# PinscapePico_KL25Z_Adapter_-_PCA9555_vsn.net
KiCad netlist of a schematic drawn in EAGLE
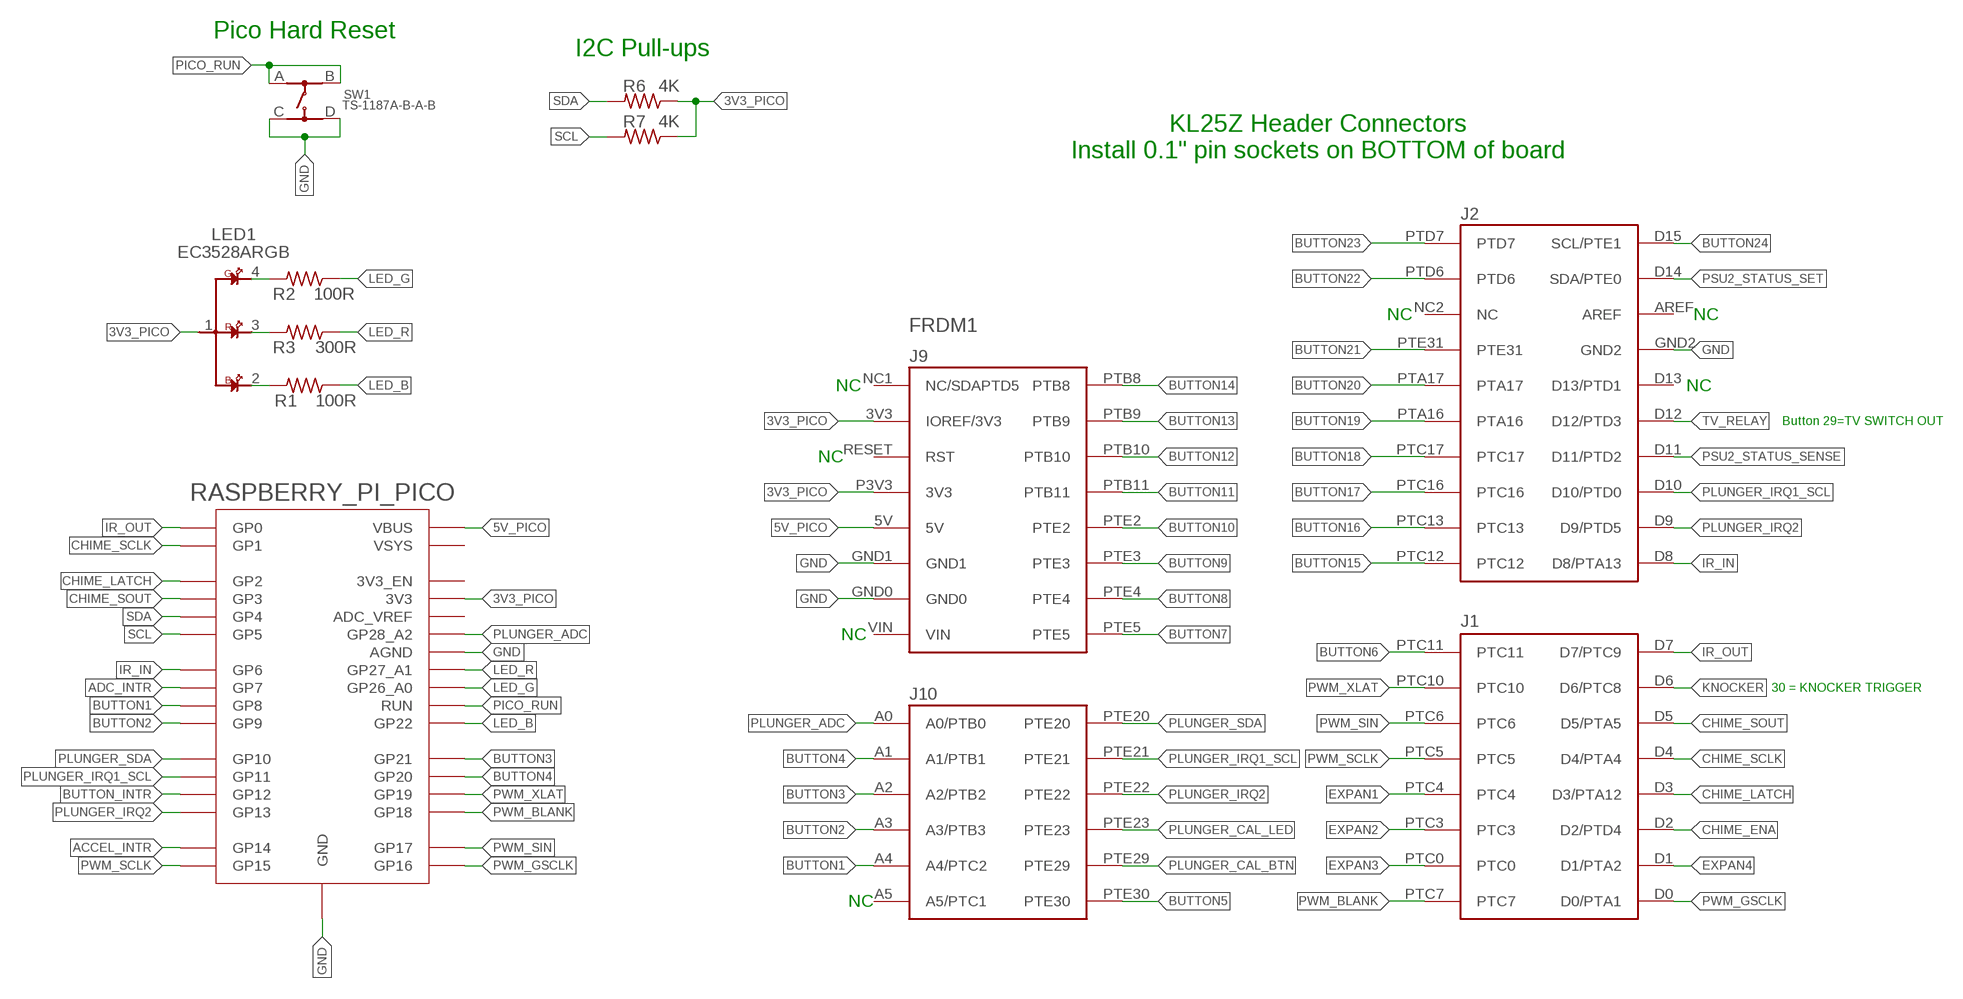
[diagram p0: schematic, sheet 1]
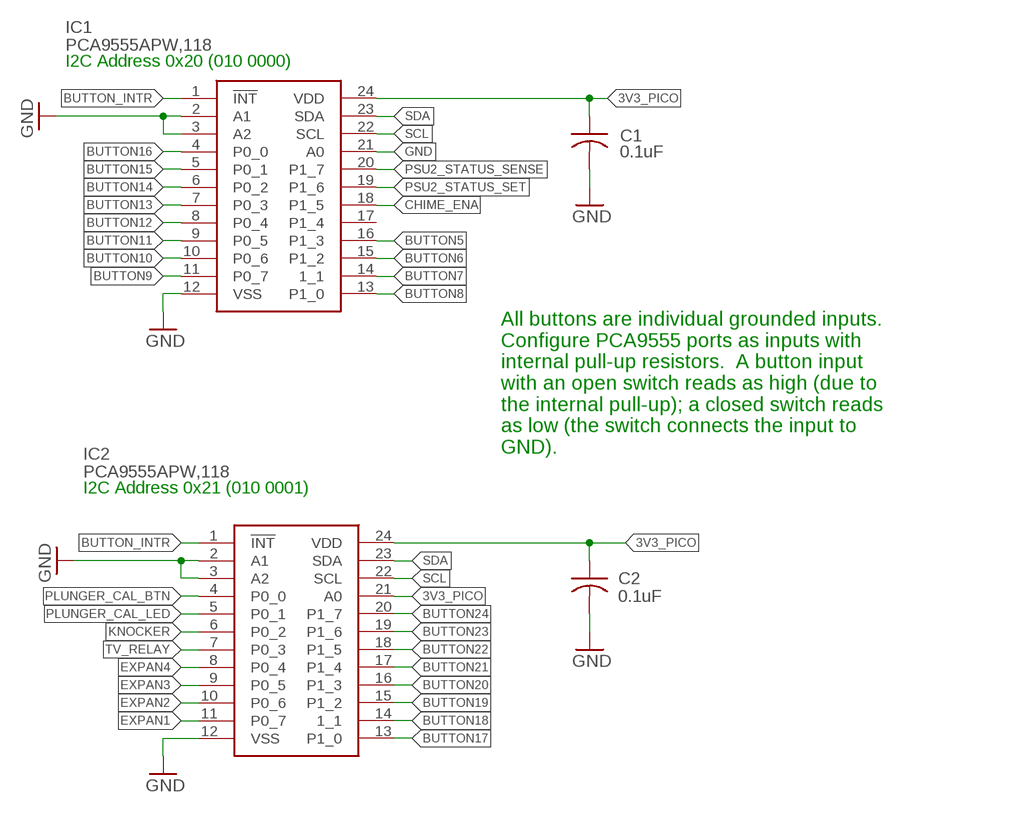
[diagram p1: schematic, sheet 2]
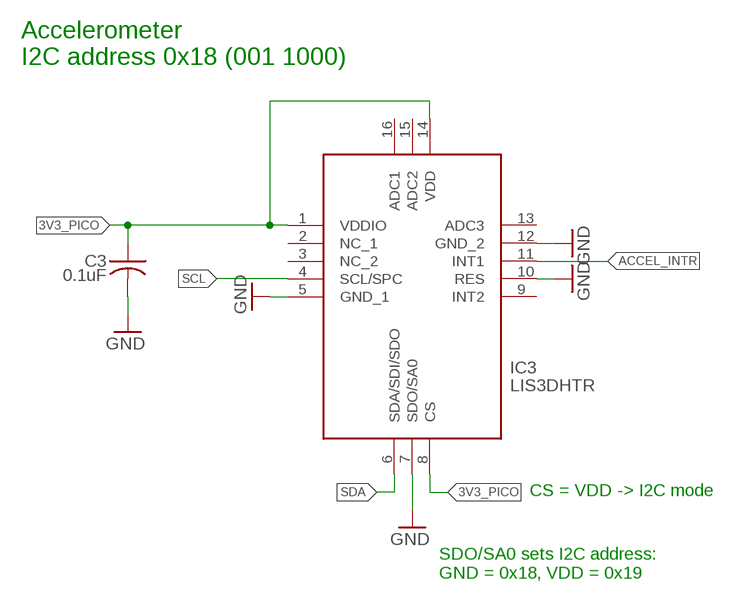
[diagram p2: schematic, sheet 3]
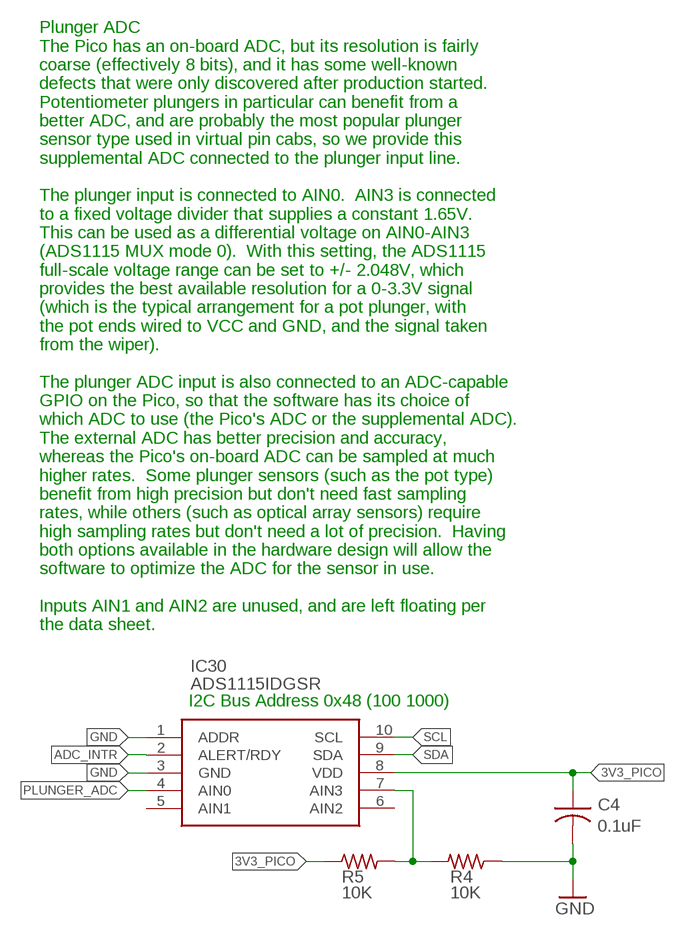
[diagram p3: schematic, sheet 4]

(export (version "E")
  (design (tool "Eeschema 10.0.6"))
  (components
    (comp (ref "C3")
      (value "0.1uF")
      (footprint "eagle-import:C1206")
      (libsource (lib "eagle-import") (part "C-USC1206"))
    )
    (comp (ref "IC3")
      (value "LIS3DHTR")
      (footprint "eagle-import:LIS3DHTR")
      (fields (field (name "MOUSER_PART_NUMBER") "511-LIS3DHTR"))
      (libsource (lib "eagle-import") (part "LIS3DHTR"))
    )
    (comp (ref "FRDM1")
      (value "KL25Z")
      (footprint "eagle-import:FRDM_KL25Z_NORMAL")
      (libsource (lib "eagle-import") (part "FRDM-KL25ZNORMAL"))
    )
    (comp (ref "LED1")
      (value "EC3528ARGB")
      (footprint "eagle-import:EC3528ARGB")
      (libsource (lib "eagle-import") (part "EC3528ARGB"))
    )
    (comp (ref "R1")
      (value "100R")
      (footprint "eagle-import:R1206")
      (libsource (lib "eagle-import") (part "R-US_R1206"))
    )
    (comp (ref "R2")
      (value "100R")
      (footprint "eagle-import:R1206")
      (libsource (lib "eagle-import") (part "R-US_R1206"))
    )
    (comp (ref "R3")
      (value "300R")
      (footprint "eagle-import:R1206")
      (libsource (lib "eagle-import") (part "R-US_R1206"))
    )
    (comp (ref "R6")
      (value "4K")
      (footprint "eagle-import:R1206")
      (libsource (lib "eagle-import") (part "R-US_R1206"))
    )
    (comp (ref "R7")
      (value "4K")
      (footprint "eagle-import:R1206")
      (libsource (lib "eagle-import") (part "R-US_R1206"))
    )
    (comp (ref "RASPBERRY_PI_PICO")
      (value "RPI_PICO_NO_DEBUG")
      (footprint "eagle-import:RPI_PICO_TH_NO_DEBUG")
      (libsource (lib "eagle-import") (part "RPI_PICO_NO_DEBUG"))
    )
    (comp (ref "SW1")
      (value "TS-1187A-B-A-B")
      (footprint "eagle-import:TS-1187A-B-A-B")
      (libsource (lib "eagle-import") (part "TS-1187A-B-A-B"))
    )
    (comp (ref "C4")
      (value "0.1uF")
      (footprint "eagle-import:C1206")
      (libsource (lib "eagle-import") (part "C-USC1206"))
    )
    (comp (ref "IC30")
      (value "ADS1115IDGSR")
      (footprint "eagle-import:SOP50P490X110-10N")
      (fields (field (name "MOUSER_PART_NUMBER") "595-ADS1115IDGSR"))
      (libsource (lib "eagle-import") (part "ADS1115IDGSR"))
    )
    (comp (ref "R4")
      (value "10K")
      (footprint "eagle-import:R1206")
      (libsource (lib "eagle-import") (part "R-US_R1206"))
    )
    (comp (ref "R5")
      (value "10K")
      (footprint "eagle-import:R1206")
      (libsource (lib "eagle-import") (part "R-US_R1206"))
    )
    (comp (ref "C1")
      (value "0.1uF")
      (footprint "eagle-import:C1206")
      (libsource (lib "eagle-import") (part "C-USC1206"))
    )
    (comp (ref "C2")
      (value "0.1uF")
      (footprint "eagle-import:C1206")
      (libsource (lib "eagle-import") (part "C-USC1206"))
    )
    (comp (ref "IC1")
      (value "PCA9555APW,118")
      (footprint "eagle-import:SOP65P640X110-24N")
      (fields (field (name "MOUSER_PART_NUMBER") "771-PCA9555APW118"))
      (libsource (lib "eagle-import") (part "PCA9555APW,118"))
    )
    (comp (ref "IC2")
      (value "PCA9555APW,118")
      (footprint "eagle-import:SOP65P640X110-24N")
      (fields (field (name "MOUSER_PART_NUMBER") "771-PCA9555APW118"))
      (libsource (lib "eagle-import") (part "PCA9555APW,118"))
    )
  )
  (nets
    (net (code "1") (name "3V3_PICO") (class "Default")
      (node (ref "C1") (pin "1") (pinfunction "1_1") (pintype "passive"))
      (node (ref "C2") (pin "1") (pinfunction "1_1") (pintype "passive"))
      (node (ref "C3") (pin "1") (pinfunction "1_1") (pintype "passive"))
      (node (ref "C4") (pin "1") (pinfunction "1_1") (pintype "passive"))
      (node (ref "FRDM1") (pin "3V3") (pinfunction "IOREF/3V3_3V3") (pintype "bidirectional"))
      (node (ref "FRDM1") (pin "P3V3") (pinfunction "3V3_P3V3") (pintype "bidirectional"))
      (node (ref "IC1") (pin "24") (pinfunction "VDD_24") (pintype "bidirectional"))
      (node (ref "IC2") (pin "21") (pinfunction "A0_21") (pintype "bidirectional"))
      (node (ref "IC2") (pin "24") (pinfunction "VDD_24") (pintype "bidirectional"))
      (node (ref "IC3") (pin "1") (pinfunction "VDDIO_1") (pintype "power_in"))
      (node (ref "IC3") (pin "14") (pinfunction "VDD_14") (pintype "power_in"))
      (node (ref "IC3") (pin "8") (pinfunction "CS_8") (pintype "input"))
      (node (ref "IC30") (pin "8") (pinfunction "VDD_8") (pintype "bidirectional"))
      (node (ref "LED1") (pin "1") (pinfunction "1_1") (pintype "bidirectional"))
      (node (ref "R5") (pin "1") (pinfunction "1_1") (pintype "passive"))
      (node (ref "R6") (pin "1") (pinfunction "1_1") (pintype "passive"))
      (node (ref "R7") (pin "1") (pinfunction "1_1") (pintype "passive"))
      (node (ref "RASPBERRY_PI_PICO") (pin "3V3") (pinfunction "3V3_3V3") (pintype "bidirectional"))
    )
    (net (code "2") (name "5V_PICO") (class "Default")
      (node (ref "FRDM1") (pin "5V") (pinfunction "5V_5V") (pintype "bidirectional"))
      (node (ref "RASPBERRY_PI_PICO") (pin "VBUS") (pinfunction "VBUS_VBUS") (pintype "bidirectional"))
    )
    (net (code "3") (name "ACCEL_INTR") (class "Default")
      (node (ref "IC3") (pin "11") (pinfunction "INT1_11") (pintype "input"))
      (node (ref "RASPBERRY_PI_PICO") (pin "GP14") (pinfunction "GP14_GP14") (pintype "bidirectional"))
    )
    (net (code "4") (name "ADC_INTR") (class "Default")
      (node (ref "IC30") (pin "2") (pinfunction "ALERT/RDY_2") (pintype "bidirectional"))
      (node (ref "RASPBERRY_PI_PICO") (pin "GP7") (pinfunction "GP7_GP7") (pintype "bidirectional"))
    )
    (net (code "5") (name "BUTTON1") (class "Default")
      (node (ref "FRDM1") (pin "A4") (pinfunction "A4/PTC2_A4") (pintype "bidirectional"))
      (node (ref "RASPBERRY_PI_PICO") (pin "GP8") (pinfunction "GP8_GP8") (pintype "bidirectional"))
    )
    (net (code "6") (name "BUTTON2") (class "Default")
      (node (ref "FRDM1") (pin "A3") (pinfunction "A3/PTB3_A3") (pintype "bidirectional"))
      (node (ref "RASPBERRY_PI_PICO") (pin "GP9") (pinfunction "GP9_GP9") (pintype "bidirectional"))
    )
    (net (code "7") (name "BUTTON3") (class "Default")
      (node (ref "FRDM1") (pin "A2") (pinfunction "A2/PTB2_A2") (pintype "bidirectional"))
      (node (ref "RASPBERRY_PI_PICO") (pin "GP21") (pinfunction "GP21_GP21") (pintype "bidirectional"))
    )
    (net (code "8") (name "BUTTON4") (class "Default")
      (node (ref "FRDM1") (pin "A1") (pinfunction "A1/PTB1_A1") (pintype "bidirectional"))
      (node (ref "RASPBERRY_PI_PICO") (pin "GP20") (pinfunction "GP20_GP20") (pintype "bidirectional"))
    )
    (net (code "9") (name "BUTTON5") (class "Default")
      (node (ref "FRDM1") (pin "PTE30") (pinfunction "PTE30_PTE30") (pintype "bidirectional"))
      (node (ref "IC1") (pin "16") (pinfunction "P1_3_16") (pintype "bidirectional"))
    )
    (net (code "10") (name "BUTTON6") (class "Default")
      (node (ref "FRDM1") (pin "PTC11") (pinfunction "PTC11_PTC11") (pintype "bidirectional"))
      (node (ref "IC1") (pin "15") (pinfunction "P1_2_15") (pintype "bidirectional"))
    )
    (net (code "11") (name "BUTTON7") (class "Default")
      (node (ref "FRDM1") (pin "PTE5") (pinfunction "PTE5_PTE5") (pintype "bidirectional"))
      (node (ref "IC1") (pin "14") (pinfunction "1_1_14") (pintype "bidirectional"))
    )
    (net (code "12") (name "BUTTON8") (class "Default")
      (node (ref "FRDM1") (pin "PTE4") (pinfunction "PTE4_PTE4") (pintype "bidirectional"))
      (node (ref "IC1") (pin "13") (pinfunction "P1_0_13") (pintype "bidirectional"))
    )
    (net (code "13") (name "BUTTON9") (class "Default")
      (node (ref "FRDM1") (pin "PTE3") (pinfunction "PTE3_PTE3") (pintype "bidirectional"))
      (node (ref "IC1") (pin "11") (pinfunction "P0_7_11") (pintype "bidirectional"))
    )
    (net (code "14") (name "BUTTON10") (class "Default")
      (node (ref "FRDM1") (pin "PTE2") (pinfunction "PTE2_PTE2") (pintype "bidirectional"))
      (node (ref "IC1") (pin "10") (pinfunction "P0_6_10") (pintype "bidirectional"))
    )
    (net (code "15") (name "BUTTON11") (class "Default")
      (node (ref "FRDM1") (pin "PTB11") (pinfunction "PTB11_PTB11") (pintype "bidirectional"))
      (node (ref "IC1") (pin "9") (pinfunction "P0_5_9") (pintype "bidirectional"))
    )
    (net (code "16") (name "BUTTON12") (class "Default")
      (node (ref "FRDM1") (pin "PTB10") (pinfunction "PTB10_PTB10") (pintype "bidirectional"))
      (node (ref "IC1") (pin "8") (pinfunction "P0_4_8") (pintype "bidirectional"))
    )
    (net (code "17") (name "BUTTON13") (class "Default")
      (node (ref "FRDM1") (pin "PTB9") (pinfunction "PTB9_PTB9") (pintype "bidirectional"))
      (node (ref "IC1") (pin "7") (pinfunction "P0_3_7") (pintype "bidirectional"))
    )
    (net (code "18") (name "BUTTON14") (class "Default")
      (node (ref "FRDM1") (pin "PTB8") (pinfunction "PTB8_PTB8") (pintype "bidirectional"))
      (node (ref "IC1") (pin "6") (pinfunction "P0_2_6") (pintype "bidirectional"))
    )
    (net (code "19") (name "BUTTON15") (class "Default")
      (node (ref "FRDM1") (pin "PTC12") (pinfunction "PTC12_PTC12") (pintype "bidirectional"))
      (node (ref "IC1") (pin "5") (pinfunction "P0_1_5") (pintype "bidirectional"))
    )
    (net (code "20") (name "BUTTON16") (class "Default")
      (node (ref "FRDM1") (pin "PTC13") (pinfunction "PTC13_PTC13") (pintype "bidirectional"))
      (node (ref "IC1") (pin "4") (pinfunction "P0_0_4") (pintype "bidirectional"))
    )
    (net (code "21") (name "BUTTON17") (class "Default")
      (node (ref "FRDM1") (pin "PTC16") (pinfunction "PTC16_PTC16") (pintype "bidirectional"))
      (node (ref "IC2") (pin "13") (pinfunction "P1_0_13") (pintype "bidirectional"))
    )
    (net (code "22") (name "BUTTON18") (class "Default")
      (node (ref "FRDM1") (pin "PTC17") (pinfunction "PTC17_PTC17") (pintype "bidirectional"))
      (node (ref "IC2") (pin "14") (pinfunction "1_1_14") (pintype "bidirectional"))
    )
    (net (code "23") (name "BUTTON19") (class "Default")
      (node (ref "FRDM1") (pin "PTA16") (pinfunction "PTA16_PTA16") (pintype "bidirectional"))
      (node (ref "IC2") (pin "15") (pinfunction "P1_2_15") (pintype "bidirectional"))
    )
    (net (code "24") (name "BUTTON20") (class "Default")
      (node (ref "FRDM1") (pin "PTA17") (pinfunction "PTA17_PTA17") (pintype "bidirectional"))
      (node (ref "IC2") (pin "16") (pinfunction "P1_3_16") (pintype "bidirectional"))
    )
    (net (code "25") (name "BUTTON21") (class "Default")
      (node (ref "FRDM1") (pin "PTE31") (pinfunction "PTE31_PTE31") (pintype "bidirectional"))
      (node (ref "IC2") (pin "17") (pinfunction "P1_4_17") (pintype "bidirectional"))
    )
    (net (code "26") (name "BUTTON22") (class "Default")
      (node (ref "FRDM1") (pin "PTD6") (pinfunction "PTD6_PTD6") (pintype "bidirectional"))
      (node (ref "IC2") (pin "18") (pinfunction "P1_5_18") (pintype "bidirectional"))
    )
    (net (code "27") (name "BUTTON23") (class "Default")
      (node (ref "FRDM1") (pin "PTD7") (pinfunction "PTD7_PTD7") (pintype "bidirectional"))
      (node (ref "IC2") (pin "19") (pinfunction "P1_6_19") (pintype "bidirectional"))
    )
    (net (code "28") (name "BUTTON24") (class "Default")
      (node (ref "FRDM1") (pin "D15") (pinfunction "SCL/PTE1_D15") (pintype "bidirectional"))
      (node (ref "IC2") (pin "20") (pinfunction "P1_7_20") (pintype "bidirectional"))
    )
    (net (code "29") (name "BUTTON_INTR") (class "Default")
      (node (ref "IC1") (pin "1") (pinfunction "~{INT}_1") (pintype "bidirectional"))
      (node (ref "IC2") (pin "1") (pinfunction "~{INT}_1") (pintype "bidirectional"))
      (node (ref "RASPBERRY_PI_PICO") (pin "GP12") (pinfunction "GP12_GP12") (pintype "bidirectional"))
    )
    (net (code "30") (name "CHIME_ENA") (class "Default")
      (node (ref "FRDM1") (pin "D2") (pinfunction "D2/PTD4_D2") (pintype "bidirectional"))
      (node (ref "IC1") (pin "18") (pinfunction "P1_5_18") (pintype "bidirectional"))
    )
    (net (code "31") (name "CHIME_LATCH") (class "Default")
      (node (ref "FRDM1") (pin "D3") (pinfunction "D3/PTA12_D3") (pintype "bidirectional"))
      (node (ref "RASPBERRY_PI_PICO") (pin "GP2") (pinfunction "GP2_GP2") (pintype "bidirectional"))
    )
    (net (code "32") (name "CHIME_SCLK") (class "Default")
      (node (ref "FRDM1") (pin "D4") (pinfunction "D4/PTA4_D4") (pintype "bidirectional"))
      (node (ref "RASPBERRY_PI_PICO") (pin "GP1") (pinfunction "GP1_GP1") (pintype "bidirectional"))
    )
    (net (code "33") (name "CHIME_SOUT") (class "Default")
      (node (ref "FRDM1") (pin "D5") (pinfunction "D5/PTA5_D5") (pintype "bidirectional"))
      (node (ref "RASPBERRY_PI_PICO") (pin "GP3") (pinfunction "GP3_GP3") (pintype "bidirectional"))
    )
    (net (code "34") (name "EXPAN1") (class "Default")
      (node (ref "FRDM1") (pin "PTC4") (pinfunction "PTC4_PTC4") (pintype "bidirectional"))
      (node (ref "IC2") (pin "11") (pinfunction "P0_7_11") (pintype "bidirectional"))
    )
    (net (code "35") (name "EXPAN2") (class "Default")
      (node (ref "FRDM1") (pin "PTC3") (pinfunction "PTC3_PTC3") (pintype "bidirectional"))
      (node (ref "IC2") (pin "10") (pinfunction "P0_6_10") (pintype "bidirectional"))
    )
    (net (code "36") (name "EXPAN3") (class "Default")
      (node (ref "FRDM1") (pin "PTC0") (pinfunction "PTC0_PTC0") (pintype "bidirectional"))
      (node (ref "IC2") (pin "9") (pinfunction "P0_5_9") (pintype "bidirectional"))
    )
    (net (code "37") (name "EXPAN4") (class "Default")
      (node (ref "FRDM1") (pin "D1") (pinfunction "D1/PTA2_D1") (pintype "bidirectional"))
      (node (ref "IC2") (pin "8") (pinfunction "P0_4_8") (pintype "bidirectional"))
    )
    (net (code "38") (name "GND") (class "Default")
      (node (ref "C1") (pin "2") (pinfunction "2_2") (pintype "passive"))
      (node (ref "C2") (pin "2") (pinfunction "2_2") (pintype "passive"))
      (node (ref "C3") (pin "2") (pinfunction "2_2") (pintype "passive"))
      (node (ref "C4") (pin "2") (pinfunction "2_2") (pintype "passive"))
      (node (ref "FRDM1") (pin "GND0") (pinfunction "GND0_GND0") (pintype "bidirectional"))
      (node (ref "FRDM1") (pin "GND1") (pinfunction "GND1_GND1") (pintype "bidirectional"))
      (node (ref "FRDM1") (pin "GND2") (pinfunction "GND2_GND2") (pintype "bidirectional"))
      (node (ref "IC1") (pin "12") (pinfunction "VSS_12") (pintype "bidirectional"))
      (node (ref "IC1") (pin "2") (pinfunction "A1_2") (pintype "bidirectional"))
      (node (ref "IC1") (pin "21") (pinfunction "A0_21") (pintype "bidirectional"))
      (node (ref "IC1") (pin "3") (pinfunction "A2_3") (pintype "bidirectional"))
      (node (ref "IC2") (pin "12") (pinfunction "VSS_12") (pintype "bidirectional"))
      (node (ref "IC2") (pin "2") (pinfunction "A1_2") (pintype "bidirectional"))
      (node (ref "IC2") (pin "3") (pinfunction "A2_3") (pintype "bidirectional"))
      (node (ref "IC3") (pin "10") (pinfunction "RES_10") (pintype "bidirectional"))
      (node (ref "IC3") (pin "12") (pinfunction "GND_2_12") (pintype "power_in"))
      (node (ref "IC3") (pin "5") (pinfunction "GND_1_5") (pintype "power_in"))
      (node (ref "IC3") (pin "7") (pinfunction "SDO/SA0_7") (pintype "bidirectional"))
      (node (ref "IC30") (pin "1") (pinfunction "ADDR_1") (pintype "bidirectional"))
      (node (ref "IC30") (pin "3") (pinfunction "GND_3") (pintype "bidirectional"))
      (node (ref "R4") (pin "1") (pinfunction "1_1") (pintype "passive"))
      (node (ref "RASPBERRY_PI_PICO") (pin "AGND") (pinfunction "AGND_AGND") (pintype "bidirectional"))
      (node (ref "RASPBERRY_PI_PICO") (pin "GND@1") (pinfunction "GND_GND@1") (pintype "bidirectional"))
      (node (ref "RASPBERRY_PI_PICO") (pin "GND@2") (pinfunction "GND_GND@2") (pintype "bidirectional"))
      (node (ref "RASPBERRY_PI_PICO") (pin "GND@3") (pinfunction "GND_GND@3") (pintype "bidirectional"))
      (node (ref "RASPBERRY_PI_PICO") (pin "GND@4") (pinfunction "GND_GND@4") (pintype "bidirectional"))
      (node (ref "RASPBERRY_PI_PICO") (pin "GND@6") (pinfunction "GND_GND@6") (pintype "bidirectional"))
      (node (ref "RASPBERRY_PI_PICO") (pin "GND@7") (pinfunction "GND_GND@7") (pintype "bidirectional"))
      (node (ref "RASPBERRY_PI_PICO") (pin "GND@8") (pinfunction "GND_GND@8") (pintype "bidirectional"))
      (node (ref "SW1") (pin "C") (pinfunction "C_C") (pintype "bidirectional"))
      (node (ref "SW1") (pin "D") (pinfunction "D_D") (pintype "bidirectional"))
    )
    (net (code "39") (name "IR_IN") (class "Default")
      (node (ref "FRDM1") (pin "D8") (pinfunction "D8/PTA13_D8") (pintype "bidirectional"))
      (node (ref "RASPBERRY_PI_PICO") (pin "GP6") (pinfunction "GP6_GP6") (pintype "bidirectional"))
    )
    (net (code "40") (name "IR_OUT") (class "Default")
      (node (ref "FRDM1") (pin "D7") (pinfunction "D7/PTC9_D7") (pintype "bidirectional"))
      (node (ref "RASPBERRY_PI_PICO") (pin "GP0") (pinfunction "GP0_GP0") (pintype "bidirectional"))
    )
    (net (code "41") (name "KNOCKER") (class "Default")
      (node (ref "FRDM1") (pin "D6") (pinfunction "D6/PTC8_D6") (pintype "bidirectional"))
      (node (ref "IC2") (pin "6") (pinfunction "P0_2_6") (pintype "bidirectional"))
    )
    (net (code "42") (name "LED_B") (class "Default")
      (node (ref "R1") (pin "1") (pinfunction "1_1") (pintype "passive"))
      (node (ref "RASPBERRY_PI_PICO") (pin "GP22") (pinfunction "GP22_GP22") (pintype "bidirectional"))
    )
    (net (code "43") (name "LED_G") (class "Default")
      (node (ref "R2") (pin "1") (pinfunction "1_1") (pintype "passive"))
      (node (ref "RASPBERRY_PI_PICO") (pin "GP26_A0") (pinfunction "GP26_A0_GP26_A0") (pintype "bidirectional"))
    )
    (net (code "44") (name "LED_R") (class "Default")
      (node (ref "R3") (pin "1") (pinfunction "1_1") (pintype "passive"))
      (node (ref "RASPBERRY_PI_PICO") (pin "GP27_A1") (pinfunction "GP27_A1_GP27_A1") (pintype "bidirectional"))
    )
    (net (code "45") (name "Net-(IC30-AIN3)") (class "Default")
      (node (ref "IC30") (pin "7") (pinfunction "AIN3_7") (pintype "bidirectional"))
      (node (ref "R4") (pin "2") (pinfunction "2_2") (pintype "passive"))
      (node (ref "R5") (pin "2") (pinfunction "2_2") (pintype "passive"))
    )
    (net (code "46") (name "Net-(LED1-Pad2)") (class "Default")
      (node (ref "LED1") (pin "2") (pinfunction "2_2") (pintype "bidirectional"))
      (node (ref "R1") (pin "2") (pinfunction "2_2") (pintype "passive"))
    )
    (net (code "47") (name "Net-(LED1-Pad3)") (class "Default")
      (node (ref "LED1") (pin "3") (pinfunction "3_3") (pintype "bidirectional"))
      (node (ref "R3") (pin "2") (pinfunction "2_2") (pintype "passive"))
    )
    (net (code "48") (name "Net-(LED1-Pad4)") (class "Default")
      (node (ref "LED1") (pin "4") (pinfunction "4_4") (pintype "bidirectional"))
      (node (ref "R2") (pin "2") (pinfunction "2_2") (pintype "passive"))
    )
    (net (code "49") (name "PICO_RUN") (class "Default")
      (node (ref "RASPBERRY_PI_PICO") (pin "RUN") (pinfunction "RUN_RUN") (pintype "bidirectional"))
      (node (ref "SW1") (pin "A") (pinfunction "A_A") (pintype "bidirectional"))
      (node (ref "SW1") (pin "B") (pinfunction "B_B") (pintype "bidirectional"))
    )
    (net (code "50") (name "PLUNGER_ADC") (class "Default")
      (node (ref "FRDM1") (pin "A0") (pinfunction "A0/PTB0_A0") (pintype "bidirectional"))
      (node (ref "IC30") (pin "4") (pinfunction "AIN0_4") (pintype "bidirectional"))
      (node (ref "RASPBERRY_PI_PICO") (pin "GP28_A2") (pinfunction "GP28_A2_GP28_A2") (pintype "bidirectional"))
    )
    (net (code "51") (name "PLUNGER_CAL_BTN") (class "Default")
      (node (ref "FRDM1") (pin "PTE29") (pinfunction "PTE29_PTE29") (pintype "bidirectional"))
      (node (ref "IC2") (pin "4") (pinfunction "P0_0_4") (pintype "bidirectional"))
    )
    (net (code "52") (name "PLUNGER_CAL_LED") (class "Default")
      (node (ref "FRDM1") (pin "PTE23") (pinfunction "PTE23_PTE23") (pintype "bidirectional"))
      (node (ref "IC2") (pin "5") (pinfunction "P0_1_5") (pintype "bidirectional"))
    )
    (net (code "53") (name "PLUNGER_IRQ1_SCL") (class "Default")
      (node (ref "FRDM1") (pin "D10") (pinfunction "D10/PTD0_D10") (pintype "bidirectional"))
      (node (ref "FRDM1") (pin "PTE21") (pinfunction "PTE21_PTE21") (pintype "bidirectional"))
      (node (ref "RASPBERRY_PI_PICO") (pin "GP11") (pinfunction "GP11_GP11") (pintype "bidirectional"))
    )
    (net (code "54") (name "PLUNGER_IRQ2") (class "Default")
      (node (ref "FRDM1") (pin "D9") (pinfunction "D9/PTD5_D9") (pintype "bidirectional"))
      (node (ref "FRDM1") (pin "PTE22") (pinfunction "PTE22_PTE22") (pintype "bidirectional"))
      (node (ref "RASPBERRY_PI_PICO") (pin "GP13") (pinfunction "GP13_GP13") (pintype "bidirectional"))
    )
    (net (code "55") (name "PLUNGER_SDA") (class "Default")
      (node (ref "FRDM1") (pin "PTE20") (pinfunction "PTE20_PTE20") (pintype "bidirectional"))
      (node (ref "RASPBERRY_PI_PICO") (pin "GP10") (pinfunction "GP10_GP10") (pintype "bidirectional"))
    )
    (net (code "56") (name "PSU2_STATUS_SENSE") (class "Default")
      (node (ref "FRDM1") (pin "D11") (pinfunction "D11/PTD2_D11") (pintype "bidirectional"))
      (node (ref "IC1") (pin "20") (pinfunction "P1_7_20") (pintype "bidirectional"))
    )
    (net (code "57") (name "PSU2_STATUS_SET") (class "Default")
      (node (ref "FRDM1") (pin "D14") (pinfunction "SDA/PTE0_D14") (pintype "bidirectional"))
      (node (ref "IC1") (pin "19") (pinfunction "P1_6_19") (pintype "bidirectional"))
    )
    (net (code "58") (name "PWM_BLANK") (class "Default")
      (node (ref "FRDM1") (pin "PTC7") (pinfunction "PTC7_PTC7") (pintype "bidirectional"))
      (node (ref "RASPBERRY_PI_PICO") (pin "GP18") (pinfunction "GP18_GP18") (pintype "bidirectional"))
    )
    (net (code "59") (name "PWM_GSCLK") (class "Default")
      (node (ref "FRDM1") (pin "D0") (pinfunction "D0/PTA1_D0") (pintype "bidirectional"))
      (node (ref "RASPBERRY_PI_PICO") (pin "GP16") (pinfunction "GP16_GP16") (pintype "bidirectional"))
    )
    (net (code "60") (name "PWM_SCLK") (class "Default")
      (node (ref "FRDM1") (pin "PTC5") (pinfunction "PTC5_PTC5") (pintype "bidirectional"))
      (node (ref "RASPBERRY_PI_PICO") (pin "GP15") (pinfunction "GP15_GP15") (pintype "bidirectional"))
    )
    (net (code "61") (name "PWM_SIN") (class "Default")
      (node (ref "FRDM1") (pin "PTC6") (pinfunction "PTC6_PTC6") (pintype "bidirectional"))
      (node (ref "RASPBERRY_PI_PICO") (pin "GP17") (pinfunction "GP17_GP17") (pintype "bidirectional"))
    )
    (net (code "62") (name "PWM_XLAT") (class "Default")
      (node (ref "FRDM1") (pin "PTC10") (pinfunction "PTC10_PTC10") (pintype "bidirectional"))
      (node (ref "RASPBERRY_PI_PICO") (pin "GP19") (pinfunction "GP19_GP19") (pintype "bidirectional"))
    )
    (net (code "63") (name "SCL") (class "Default")
      (node (ref "IC1") (pin "22") (pinfunction "SCL_22") (pintype "bidirectional"))
      (node (ref "IC2") (pin "22") (pinfunction "SCL_22") (pintype "bidirectional"))
      (node (ref "IC3") (pin "4") (pinfunction "SCL/SPC_4") (pintype "bidirectional"))
      (node (ref "IC30") (pin "10") (pinfunction "SCL_10") (pintype "bidirectional"))
      (node (ref "R7") (pin "2") (pinfunction "2_2") (pintype "passive"))
      (node (ref "RASPBERRY_PI_PICO") (pin "GP5") (pinfunction "GP5_GP5") (pintype "bidirectional"))
    )
    (net (code "64") (name "SDA") (class "Default")
      (node (ref "IC1") (pin "23") (pinfunction "SDA_23") (pintype "bidirectional"))
      (node (ref "IC2") (pin "23") (pinfunction "SDA_23") (pintype "bidirectional"))
      (node (ref "IC3") (pin "6") (pinfunction "SDA/SDI/SDO_6") (pintype "bidirectional"))
      (node (ref "IC30") (pin "9") (pinfunction "SDA_9") (pintype "bidirectional"))
      (node (ref "R6") (pin "2") (pinfunction "2_2") (pintype "passive"))
      (node (ref "RASPBERRY_PI_PICO") (pin "GP4") (pinfunction "GP4_GP4") (pintype "bidirectional"))
    )
    (net (code "65") (name "TV_RELAY") (class "Default")
      (node (ref "FRDM1") (pin "D12") (pinfunction "D12/PTD3_D12") (pintype "bidirectional"))
      (node (ref "IC2") (pin "7") (pinfunction "P0_3_7") (pintype "bidirectional"))
    )
    (net (code "66") (name "unconnected-(FRDM1-A5{slash}PTC1-PadA5)") (class "Default")
      (node (ref "FRDM1") (pin "A5") (pinfunction "A5/PTC1_A5") (pintype "bidirectional"))
    )
    (net (code "67") (name "unconnected-(FRDM1-D13{slash}PTD1-PadD13)") (class "Default")
      (node (ref "FRDM1") (pin "D13") (pinfunction "D13/PTD1_D13") (pintype "bidirectional"))
    )
    (net (code "68") (name "unconnected-(FRDM1-NC-PadNC2)") (class "Default")
      (node (ref "FRDM1") (pin "NC2") (pinfunction "NC_NC2") (pintype "bidirectional"))
    )
    (net (code "69") (name "unconnected-(FRDM1-NC{slash}SDAPTD5-PadNC1)") (class "Default")
      (node (ref "FRDM1") (pin "NC1") (pinfunction "NC/SDAPTD5_NC1") (pintype "bidirectional"))
    )
    (net (code "70") (name "unconnected-(FRDM1-PadAREF)") (class "Default")
      (node (ref "FRDM1") (pin "AREF") (pinfunction "AREF_AREF") (pintype "bidirectional"))
    )
    (net (code "71") (name "unconnected-(FRDM1-PadVIN)") (class "Default")
      (node (ref "FRDM1") (pin "VIN") (pinfunction "VIN_VIN") (pintype "bidirectional"))
    )
    (net (code "72") (name "unconnected-(FRDM1-RST-PadRESET)") (class "Default")
      (node (ref "FRDM1") (pin "RESET") (pinfunction "RST_RESET") (pintype "bidirectional"))
    )
    (net (code "73") (name "unconnected-(IC1-P1_4-Pad17)") (class "Default")
      (node (ref "IC1") (pin "17") (pinfunction "P1_4_17") (pintype "bidirectional"))
    )
    (net (code "74") (name "unconnected-(IC3-ADC1-Pad16)") (class "Default")
      (node (ref "IC3") (pin "16") (pinfunction "ADC1_16") (pintype "bidirectional"))
    )
    (net (code "75") (name "unconnected-(IC3-ADC2-Pad15)") (class "Default")
      (node (ref "IC3") (pin "15") (pinfunction "ADC2_15") (pintype "bidirectional"))
    )
    (net (code "76") (name "unconnected-(IC3-ADC3-Pad13)") (class "Default")
      (node (ref "IC3") (pin "13") (pinfunction "ADC3_13") (pintype "bidirectional"))
    )
    (net (code "77") (name "unconnected-(IC3-INT2-Pad9)") (class "Default")
      (node (ref "IC3") (pin "9") (pinfunction "INT2_9") (pintype "input"))
    )
    (net (code "78") (name "unconnected-(IC3-NC_1-Pad2)") (class "Default")
      (node (ref "IC3") (pin "2") (pinfunction "NC_1_2") (pintype "bidirectional"))
    )
    (net (code "79") (name "unconnected-(IC3-NC_2-Pad3)") (class "Default")
      (node (ref "IC3") (pin "3") (pinfunction "NC_2_3") (pintype "bidirectional"))
    )
    (net (code "80") (name "unconnected-(IC30-AIN1-Pad5)") (class "Default")
      (node (ref "IC30") (pin "5") (pinfunction "AIN1_5") (pintype "bidirectional"))
    )
    (net (code "81") (name "unconnected-(IC30-AIN2-Pad6)") (class "Default")
      (node (ref "IC30") (pin "6") (pinfunction "AIN2_6") (pintype "bidirectional"))
    )
    (net (code "82") (name "unconnected-(RASPBERRY_PI_PICO-Pad3V3_EN)") (class "Default")
      (node (ref "RASPBERRY_PI_PICO") (pin "3V3_EN") (pinfunction "3V3_EN_3V3_EN") (pintype "bidirectional"))
    )
    (net (code "83") (name "unconnected-(RASPBERRY_PI_PICO-PadADC_VREF)") (class "Default")
      (node (ref "RASPBERRY_PI_PICO") (pin "ADC_VREF") (pinfunction "ADC_VREF_ADC_VREF") (pintype "bidirectional"))
    )
    (net (code "84") (name "unconnected-(RASPBERRY_PI_PICO-PadVSYS)") (class "Default")
      (node (ref "RASPBERRY_PI_PICO") (pin "VSYS") (pinfunction "VSYS_VSYS") (pintype "bidirectional"))
    )
  )
)
